# Transmitter_11-16.net
KiCad netlist of a schematic drawn in EAGLE
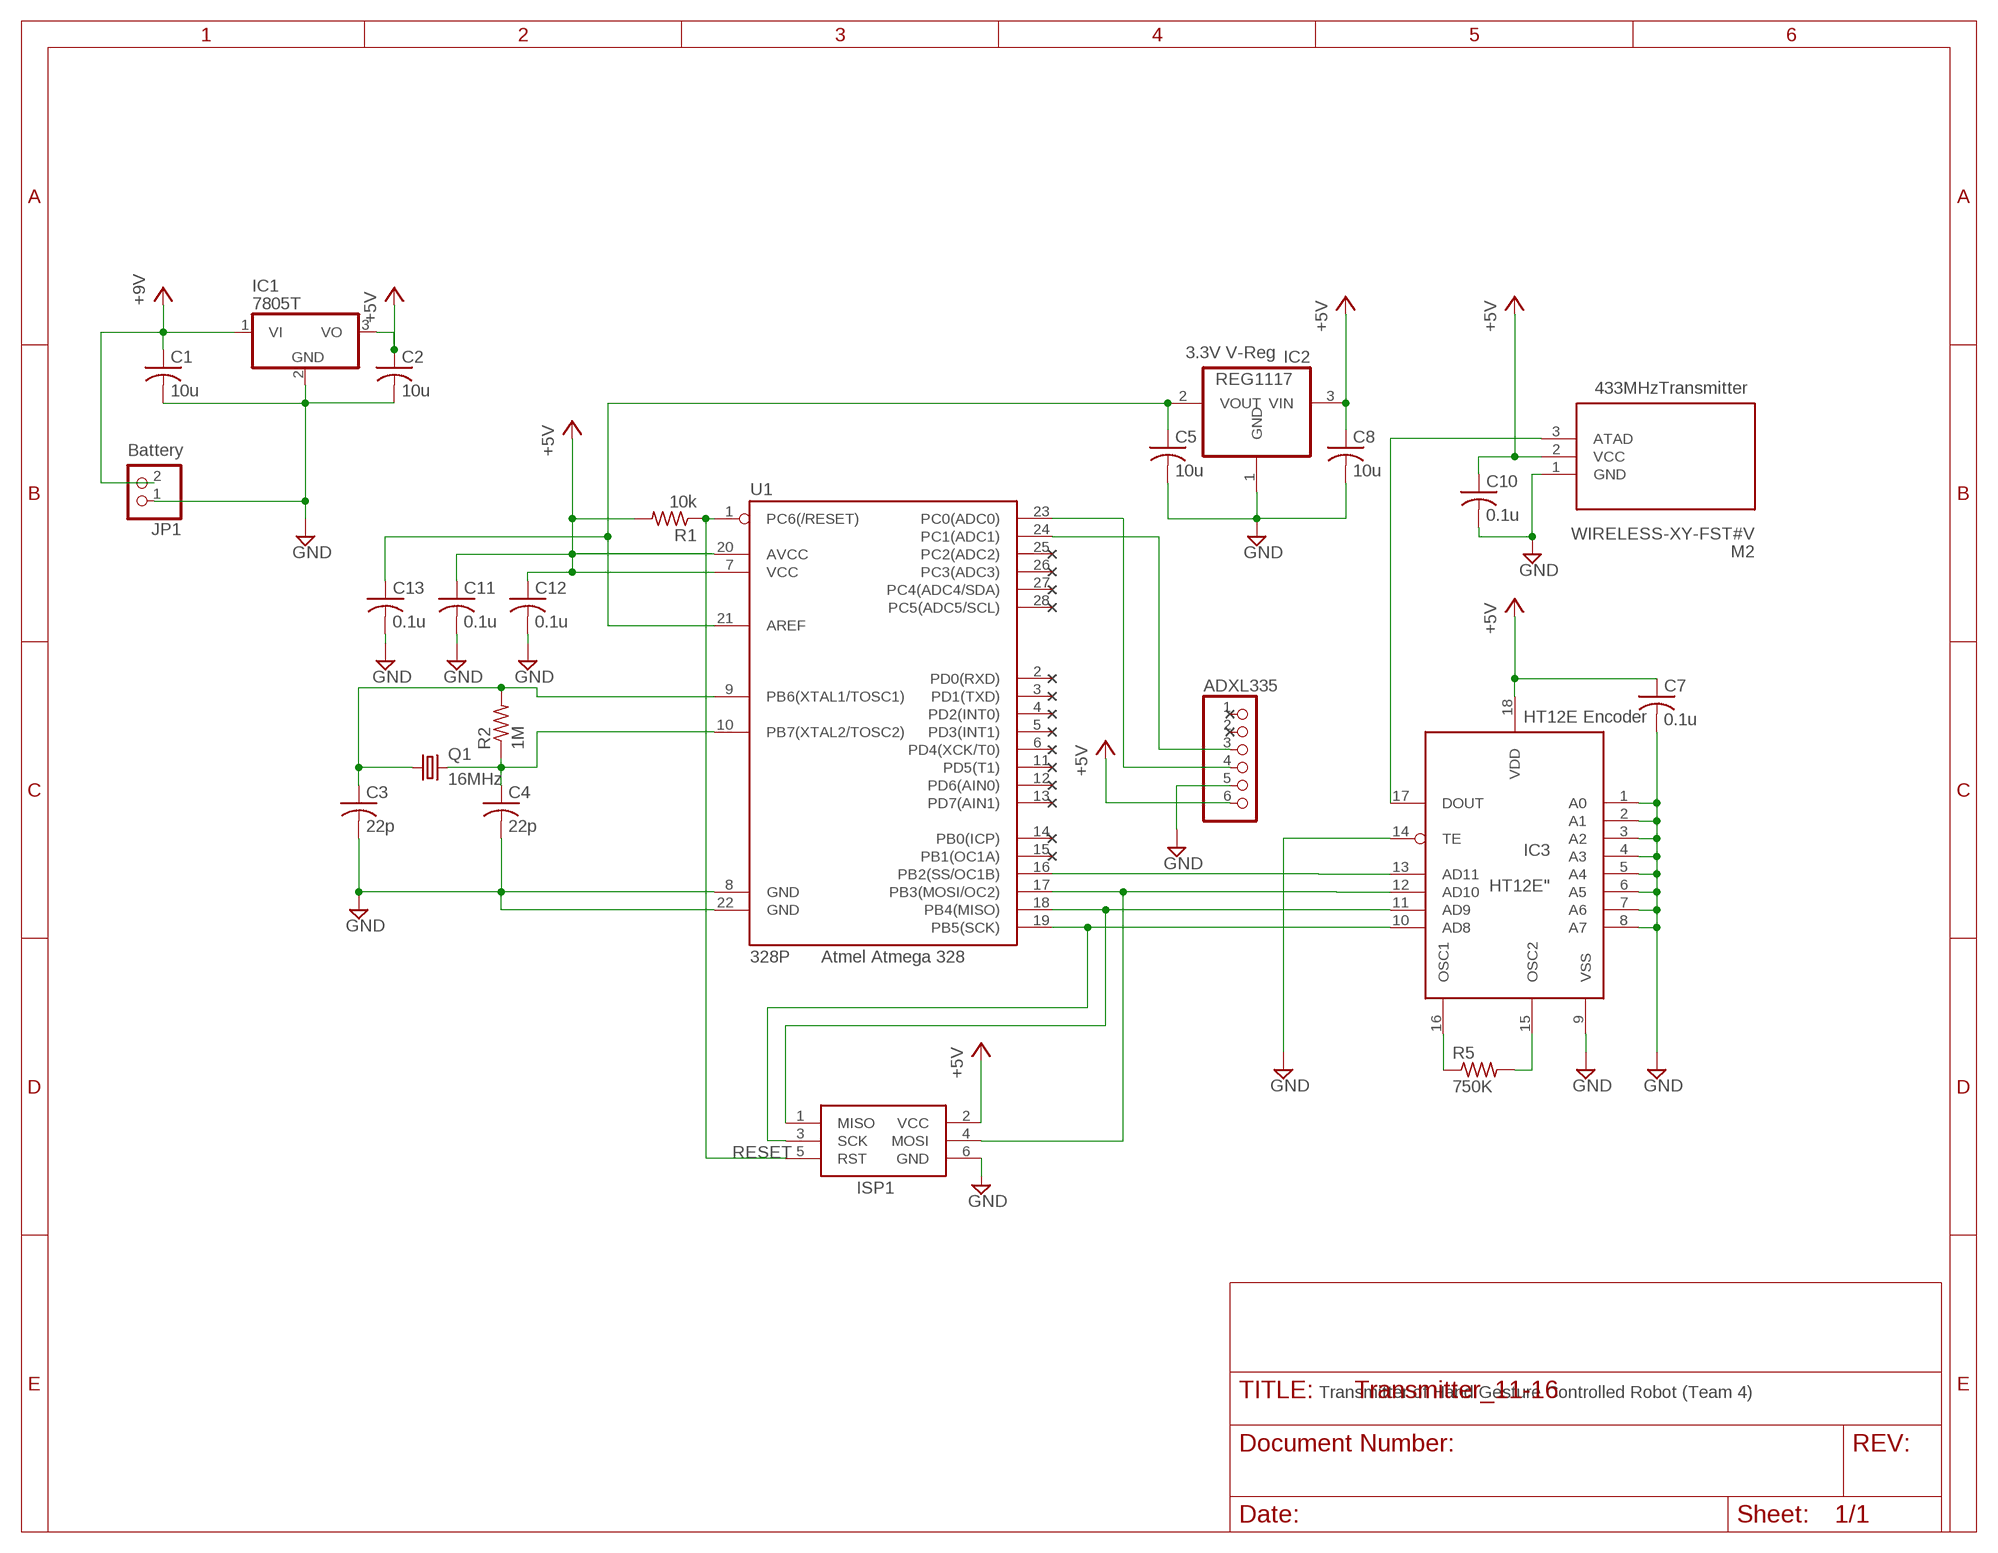
[diagram p0: schematic, sheet 1]

(export (version "E")
  (design (tool "Eeschema 10.0.6"))
  (components
    (comp (ref "ADXL335")
      (value "PINHD-1X6")
      (footprint "eagle-import:1X06")
      (libsource (lib "eagle-import") (part "PINHD-1X6"))
    )
    (comp (ref "C1")
      (value "10u")
      (footprint "eagle-import:C0805")
      (libsource (lib "eagle-import") (part "C-USC0805"))
    )
    (comp (ref "C2")
      (value "10u")
      (footprint "eagle-import:C0805")
      (libsource (lib "eagle-import") (part "C-USC0805"))
    )
    (comp (ref "C3")
      (value "22p")
      (footprint "eagle-import:C0805")
      (libsource (lib "eagle-import") (part "C-USC0805"))
    )
    (comp (ref "C4")
      (value "22p")
      (footprint "eagle-import:C0805")
      (libsource (lib "eagle-import") (part "C-USC0805"))
    )
    (comp (ref "C5")
      (value "10u")
      (footprint "eagle-import:C0805")
      (libsource (lib "eagle-import") (part "C-USC0805"))
    )
    (comp (ref "C7")
      (value "0.1u")
      (footprint "eagle-import:C0805")
      (libsource (lib "eagle-import") (part "C-USC0805"))
    )
    (comp (ref "C8")
      (value "10u")
      (footprint "eagle-import:C0805")
      (libsource (lib "eagle-import") (part "C-USC0805"))
    )
    (comp (ref "C10")
      (value "0.1u")
      (footprint "eagle-import:C0805")
      (libsource (lib "eagle-import") (part "C-USC0805"))
    )
    (comp (ref "C11")
      (value "0.1u")
      (footprint "eagle-import:C0805")
      (libsource (lib "eagle-import") (part "C-USC0805"))
    )
    (comp (ref "C12")
      (value "0.1u")
      (footprint "eagle-import:C0805")
      (libsource (lib "eagle-import") (part "C-USC0805"))
    )
    (comp (ref "C13")
      (value "0.1u")
      (footprint "eagle-import:C0805")
      (libsource (lib "eagle-import") (part "C-USC0805"))
    )
    (comp (ref "IC1")
      (value "7805T")
      (footprint "eagle-import:TO220H")
      (libsource (lib "eagle-import") (part "78T05"))
    )
    (comp (ref "IC2")
      (value "REG1117")
      (footprint "eagle-import:SOT223")
      (libsource (lib "eagle-import") (part "REG1117"))
    )
    (comp (ref "IC3")
      (value "HT12E\"")
      (footprint "eagle-import:18-DIP-A")
      (libsource (lib "eagle-import") (part "HT12E{dblquote}"))
    )
    (comp (ref "ISP1")
      (value "AVRISP-6")
      (footprint "eagle-import:AVRISP")
      (libsource (lib "eagle-import") (part "AVRISP-6"))
    )
    (comp (ref "JP1")
      (value "PINHD-1X2")
      (footprint "eagle-import:1X02")
      (libsource (lib "eagle-import") (part "PINHD-1X2"))
    )
    (comp (ref "M2")
      (value "WIRELESS-XY-FST#V")
      (footprint "eagle-import:WIRELESS-XY-FST#V")
      (libsource (lib "eagle-import") (part "WIRELESS-XY-FST#V"))
    )
    (comp (ref "Q1")
      (value "16MHz")
      (footprint "eagle-import:HC49_S")
      (libsource (lib "eagle-import") (part "CRYTALHC49S"))
    )
    (comp (ref "R1")
      (value "10k")
      (footprint "eagle-import:R0805")
      (libsource (lib "eagle-import") (part "R-US_R0805"))
    )
    (comp (ref "R2")
      (value "1M")
      (footprint "eagle-import:R0805")
      (libsource (lib "eagle-import") (part "R-US_R0805"))
    )
    (comp (ref "R5")
      (value "750K")
      (footprint "eagle-import:R0805")
      (libsource (lib "eagle-import") (part "R-US_R0805"))
    )
    (comp (ref "U1")
      (value "328P")
      (footprint "eagle-import:DIP28")
      (libsource (lib "eagle-import") (part "ATMEGA328P_PDIP"))
    )
  )
  (nets
    (net (code "1") (name "+5V") (class "Default")
      (node (ref "ADXL335") (pin "6") (pinfunction "6_6") (pintype "passive"))
      (node (ref "C10") (pin "1") (pinfunction "1_1") (pintype "passive"))
      (node (ref "C11") (pin "1") (pinfunction "1_1") (pintype "passive"))
      (node (ref "C12") (pin "1") (pinfunction "1_1") (pintype "passive"))
      (node (ref "C2") (pin "1") (pinfunction "1_1") (pintype "passive"))
      (node (ref "C7") (pin "1") (pinfunction "1_1") (pintype "passive"))
      (node (ref "C8") (pin "1") (pinfunction "1_1") (pintype "passive"))
      (node (ref "IC1") (pin "3") (pinfunction "VO_3") (pintype "passive"))
      (node (ref "IC2") (pin "3") (pinfunction "VIN_3") (pintype "input"))
      (node (ref "IC3") (pin "18") (pinfunction "VDD_18") (pintype "power_in"))
      (node (ref "ISP1") (pin "2") (pinfunction "VCC_2") (pintype "power_in"))
      (node (ref "M2") (pin "2") (pinfunction "VCC_2") (pintype "power_in"))
      (node (ref "R1") (pin "2") (pinfunction "2_2") (pintype "passive"))
      (node (ref "U1") (pin "20") (pinfunction "AVCC_20") (pintype "bidirectional"))
      (node (ref "U1") (pin "7") (pinfunction "VCC_7") (pintype "bidirectional"))
    )
    (net (code "2") (name "+9V") (class "Default")
      (node (ref "C1") (pin "1") (pinfunction "1_1") (pintype "passive"))
      (node (ref "IC1") (pin "1") (pinfunction "VI_1") (pintype "input"))
      (node (ref "JP1") (pin "2") (pinfunction "2_2") (pintype "passive"))
    )
    (net (code "3") (name "/RESET") (class "Default")
      (node (ref "ISP1") (pin "5") (pinfunction "RST_5") (pintype "output"))
      (node (ref "R1") (pin "1") (pinfunction "1_1") (pintype "passive"))
      (node (ref "U1") (pin "1") (pinfunction "PC6(/RESET)_1") (pintype "bidirectional"))
    )
    (net (code "4") (name "GND") (class "Default")
      (node (ref "ADXL335") (pin "5") (pinfunction "5_5") (pintype "passive"))
      (node (ref "C1") (pin "2") (pinfunction "2_2") (pintype "passive"))
      (node (ref "C10") (pin "2") (pinfunction "2_2") (pintype "passive"))
      (node (ref "C11") (pin "2") (pinfunction "2_2") (pintype "passive"))
      (node (ref "C12") (pin "2") (pinfunction "2_2") (pintype "passive"))
      (node (ref "C13") (pin "2") (pinfunction "2_2") (pintype "passive"))
      (node (ref "C2") (pin "2") (pinfunction "2_2") (pintype "passive"))
      (node (ref "C3") (pin "2") (pinfunction "2_2") (pintype "passive"))
      (node (ref "C4") (pin "2") (pinfunction "2_2") (pintype "passive"))
      (node (ref "C5") (pin "2") (pinfunction "2_2") (pintype "passive"))
      (node (ref "C7") (pin "2") (pinfunction "2_2") (pintype "passive"))
      (node (ref "C8") (pin "2") (pinfunction "2_2") (pintype "passive"))
      (node (ref "IC1") (pin "2") (pinfunction "GND_2") (pintype "passive"))
      (node (ref "IC2") (pin "1") (pinfunction "GND_1") (pintype "power_in"))
      (node (ref "IC3") (pin "1") (pinfunction "A0_1") (pintype "input"))
      (node (ref "IC3") (pin "14") (pinfunction "TE_14") (pintype "power_in"))
      (node (ref "IC3") (pin "2") (pinfunction "A1_2") (pintype "input"))
      (node (ref "IC3") (pin "3") (pinfunction "A2_3") (pintype "input"))
      (node (ref "IC3") (pin "4") (pinfunction "A3_4") (pintype "input"))
      (node (ref "IC3") (pin "5") (pinfunction "A4_5") (pintype "input"))
      (node (ref "IC3") (pin "6") (pinfunction "A5_6") (pintype "input"))
      (node (ref "IC3") (pin "7") (pinfunction "A6_7") (pintype "input"))
      (node (ref "IC3") (pin "8") (pinfunction "A7_8") (pintype "input"))
      (node (ref "IC3") (pin "9") (pinfunction "VSS_9") (pintype "power_in"))
      (node (ref "ISP1") (pin "6") (pinfunction "GND_6") (pintype "power_in"))
      (node (ref "JP1") (pin "1") (pinfunction "1_1") (pintype "passive"))
      (node (ref "M2") (pin "1") (pinfunction "GND_1") (pintype "power_in"))
      (node (ref "U1") (pin "22") (pinfunction "GND_22") (pintype "bidirectional"))
      (node (ref "U1") (pin "8") (pinfunction "GND_8") (pintype "bidirectional"))
    )
    (net (code "5") (name "Net-(IC2-VOUT)") (class "Default")
      (node (ref "C13") (pin "1") (pinfunction "1_1") (pintype "passive"))
      (node (ref "C5") (pin "1") (pinfunction "1_1") (pintype "passive"))
      (node (ref "IC2") (pin "2") (pinfunction "VOUT_2") (pintype "output"))
      (node (ref "U1") (pin "21") (pinfunction "AREF_21") (pintype "bidirectional"))
    )
    (net (code "6") (name "Net-(IC3-AD8)") (class "Default")
      (node (ref "IC3") (pin "10") (pinfunction "AD8_10") (pintype "input"))
      (node (ref "ISP1") (pin "3") (pinfunction "SCK_3") (pintype "output"))
      (node (ref "U1") (pin "19") (pinfunction "PB5(SCK)_19") (pintype "bidirectional"))
    )
    (net (code "7") (name "Net-(IC3-AD9)") (class "Default")
      (node (ref "IC3") (pin "11") (pinfunction "AD9_11") (pintype "input"))
      (node (ref "ISP1") (pin "1") (pinfunction "MISO_1") (pintype "input"))
      (node (ref "U1") (pin "18") (pinfunction "PB4(MISO)_18") (pintype "bidirectional"))
    )
    (net (code "8") (name "Net-(IC3-AD10)") (class "Default")
      (node (ref "IC3") (pin "12") (pinfunction "AD10_12") (pintype "input"))
      (node (ref "ISP1") (pin "4") (pinfunction "MOSI_4") (pintype "output"))
      (node (ref "U1") (pin "17") (pinfunction "PB3(MOSI/OC2)_17") (pintype "bidirectional"))
    )
    (net (code "9") (name "Net-(IC3-AD11)") (class "Default")
      (node (ref "IC3") (pin "13") (pinfunction "AD11_13") (pintype "input"))
      (node (ref "U1") (pin "16") (pinfunction "PB2(SS/OC1B)_16") (pintype "bidirectional"))
    )
    (net (code "10") (name "Net-(IC3-DOUT)") (class "Default")
      (node (ref "IC3") (pin "17") (pinfunction "DOUT_17") (pintype "output"))
      (node (ref "M2") (pin "3") (pinfunction "ATAD_3") (pintype "input"))
    )
    (net (code "11") (name "Net-(IC3-OSC1)") (class "Default")
      (node (ref "IC3") (pin "16") (pinfunction "OSC1_16") (pintype "input"))
      (node (ref "R5") (pin "1") (pinfunction "1_1") (pintype "passive"))
    )
    (net (code "12") (name "Net-(IC3-OSC2)") (class "Default")
      (node (ref "IC3") (pin "15") (pinfunction "OSC2_15") (pintype "input"))
      (node (ref "R5") (pin "2") (pinfunction "2_2") (pintype "passive"))
    )
    (net (code "13") (name "Net-(U1-PB6(XTAL1{slash}TOSC1))") (class "Default")
      (node (ref "C3") (pin "1") (pinfunction "1_1") (pintype "passive"))
      (node (ref "Q1") (pin "1") (pinfunction "1_1") (pintype "passive"))
      (node (ref "R2") (pin "2") (pinfunction "2_2") (pintype "passive"))
      (node (ref "U1") (pin "9") (pinfunction "PB6(XTAL1/TOSC1)_9") (pintype "bidirectional"))
    )
    (net (code "14") (name "Net-(U1-PB7(XTAL2{slash}TOSC2))") (class "Default")
      (node (ref "C4") (pin "1") (pinfunction "1_1") (pintype "passive"))
      (node (ref "Q1") (pin "2") (pinfunction "2_2") (pintype "passive"))
      (node (ref "R2") (pin "1") (pinfunction "1_1") (pintype "passive"))
      (node (ref "U1") (pin "10") (pinfunction "PB7(XTAL2/TOSC2)_10") (pintype "bidirectional"))
    )
    (net (code "15") (name "Net-(U1-PC0(ADC0))") (class "Default")
      (node (ref "ADXL335") (pin "4") (pinfunction "4_4") (pintype "passive"))
      (node (ref "U1") (pin "23") (pinfunction "PC0(ADC0)_23") (pintype "bidirectional"))
    )
    (net (code "16") (name "Net-(U1-PC1(ADC1))") (class "Default")
      (node (ref "ADXL335") (pin "3") (pinfunction "3_3") (pintype "passive"))
      (node (ref "U1") (pin "24") (pinfunction "PC1(ADC1)_24") (pintype "bidirectional"))
    )
    (net (code "17") (name "unconnected-(ADXL335-Pad1)") (class "Default")
      (node (ref "ADXL335") (pin "1") (pinfunction "1_1") (pintype "passive"))
    )
    (net (code "18") (name "unconnected-(ADXL335-Pad2)") (class "Default")
      (node (ref "ADXL335") (pin "2") (pinfunction "2_2") (pintype "passive"))
    )
    (net (code "19") (name "unconnected-(U1-PB0(ICP)-Pad14)") (class "Default")
      (node (ref "U1") (pin "14") (pinfunction "PB0(ICP)_14") (pintype "bidirectional"))
    )
    (net (code "20") (name "unconnected-(U1-PB1(OC1A)-Pad15)") (class "Default")
      (node (ref "U1") (pin "15") (pinfunction "PB1(OC1A)_15") (pintype "bidirectional"))
    )
    (net (code "21") (name "unconnected-(U1-PC2(ADC2)-Pad25)") (class "Default")
      (node (ref "U1") (pin "25") (pinfunction "PC2(ADC2)_25") (pintype "bidirectional"))
    )
    (net (code "22") (name "unconnected-(U1-PC3(ADC3)-Pad26)") (class "Default")
      (node (ref "U1") (pin "26") (pinfunction "PC3(ADC3)_26") (pintype "bidirectional"))
    )
    (net (code "23") (name "unconnected-(U1-PC4(ADC4{slash}SDA)-Pad27)") (class "Default")
      (node (ref "U1") (pin "27") (pinfunction "PC4(ADC4/SDA)_27") (pintype "bidirectional"))
    )
    (net (code "24") (name "unconnected-(U1-PC5(ADC5{slash}SCL)-Pad28)") (class "Default")
      (node (ref "U1") (pin "28") (pinfunction "PC5(ADC5/SCL)_28") (pintype "bidirectional"))
    )
    (net (code "25") (name "unconnected-(U1-PD0(RXD)-Pad2)") (class "Default")
      (node (ref "U1") (pin "2") (pinfunction "PD0(RXD)_2") (pintype "bidirectional"))
    )
    (net (code "26") (name "unconnected-(U1-PD1(TXD)-Pad3)") (class "Default")
      (node (ref "U1") (pin "3") (pinfunction "PD1(TXD)_3") (pintype "bidirectional"))
    )
    (net (code "27") (name "unconnected-(U1-PD2(INT0)-Pad4)") (class "Default")
      (node (ref "U1") (pin "4") (pinfunction "PD2(INT0)_4") (pintype "bidirectional"))
    )
    (net (code "28") (name "unconnected-(U1-PD3(INT1)-Pad5)") (class "Default")
      (node (ref "U1") (pin "5") (pinfunction "PD3(INT1)_5") (pintype "bidirectional"))
    )
    (net (code "29") (name "unconnected-(U1-PD4(XCK{slash}T0)-Pad6)") (class "Default")
      (node (ref "U1") (pin "6") (pinfunction "PD4(XCK/T0)_6") (pintype "bidirectional"))
    )
    (net (code "30") (name "unconnected-(U1-PD5(T1)-Pad11)") (class "Default")
      (node (ref "U1") (pin "11") (pinfunction "PD5(T1)_11") (pintype "bidirectional"))
    )
    (net (code "31") (name "unconnected-(U1-PD6(AIN0)-Pad12)") (class "Default")
      (node (ref "U1") (pin "12") (pinfunction "PD6(AIN0)_12") (pintype "bidirectional"))
    )
    (net (code "32") (name "unconnected-(U1-PD7(AIN1)-Pad13)") (class "Default")
      (node (ref "U1") (pin "13") (pinfunction "PD7(AIN1)_13") (pintype "bidirectional"))
    )
  )
)
